# filters_V1_1.net
KiCad netlist of a schematic drawn in EAGLE
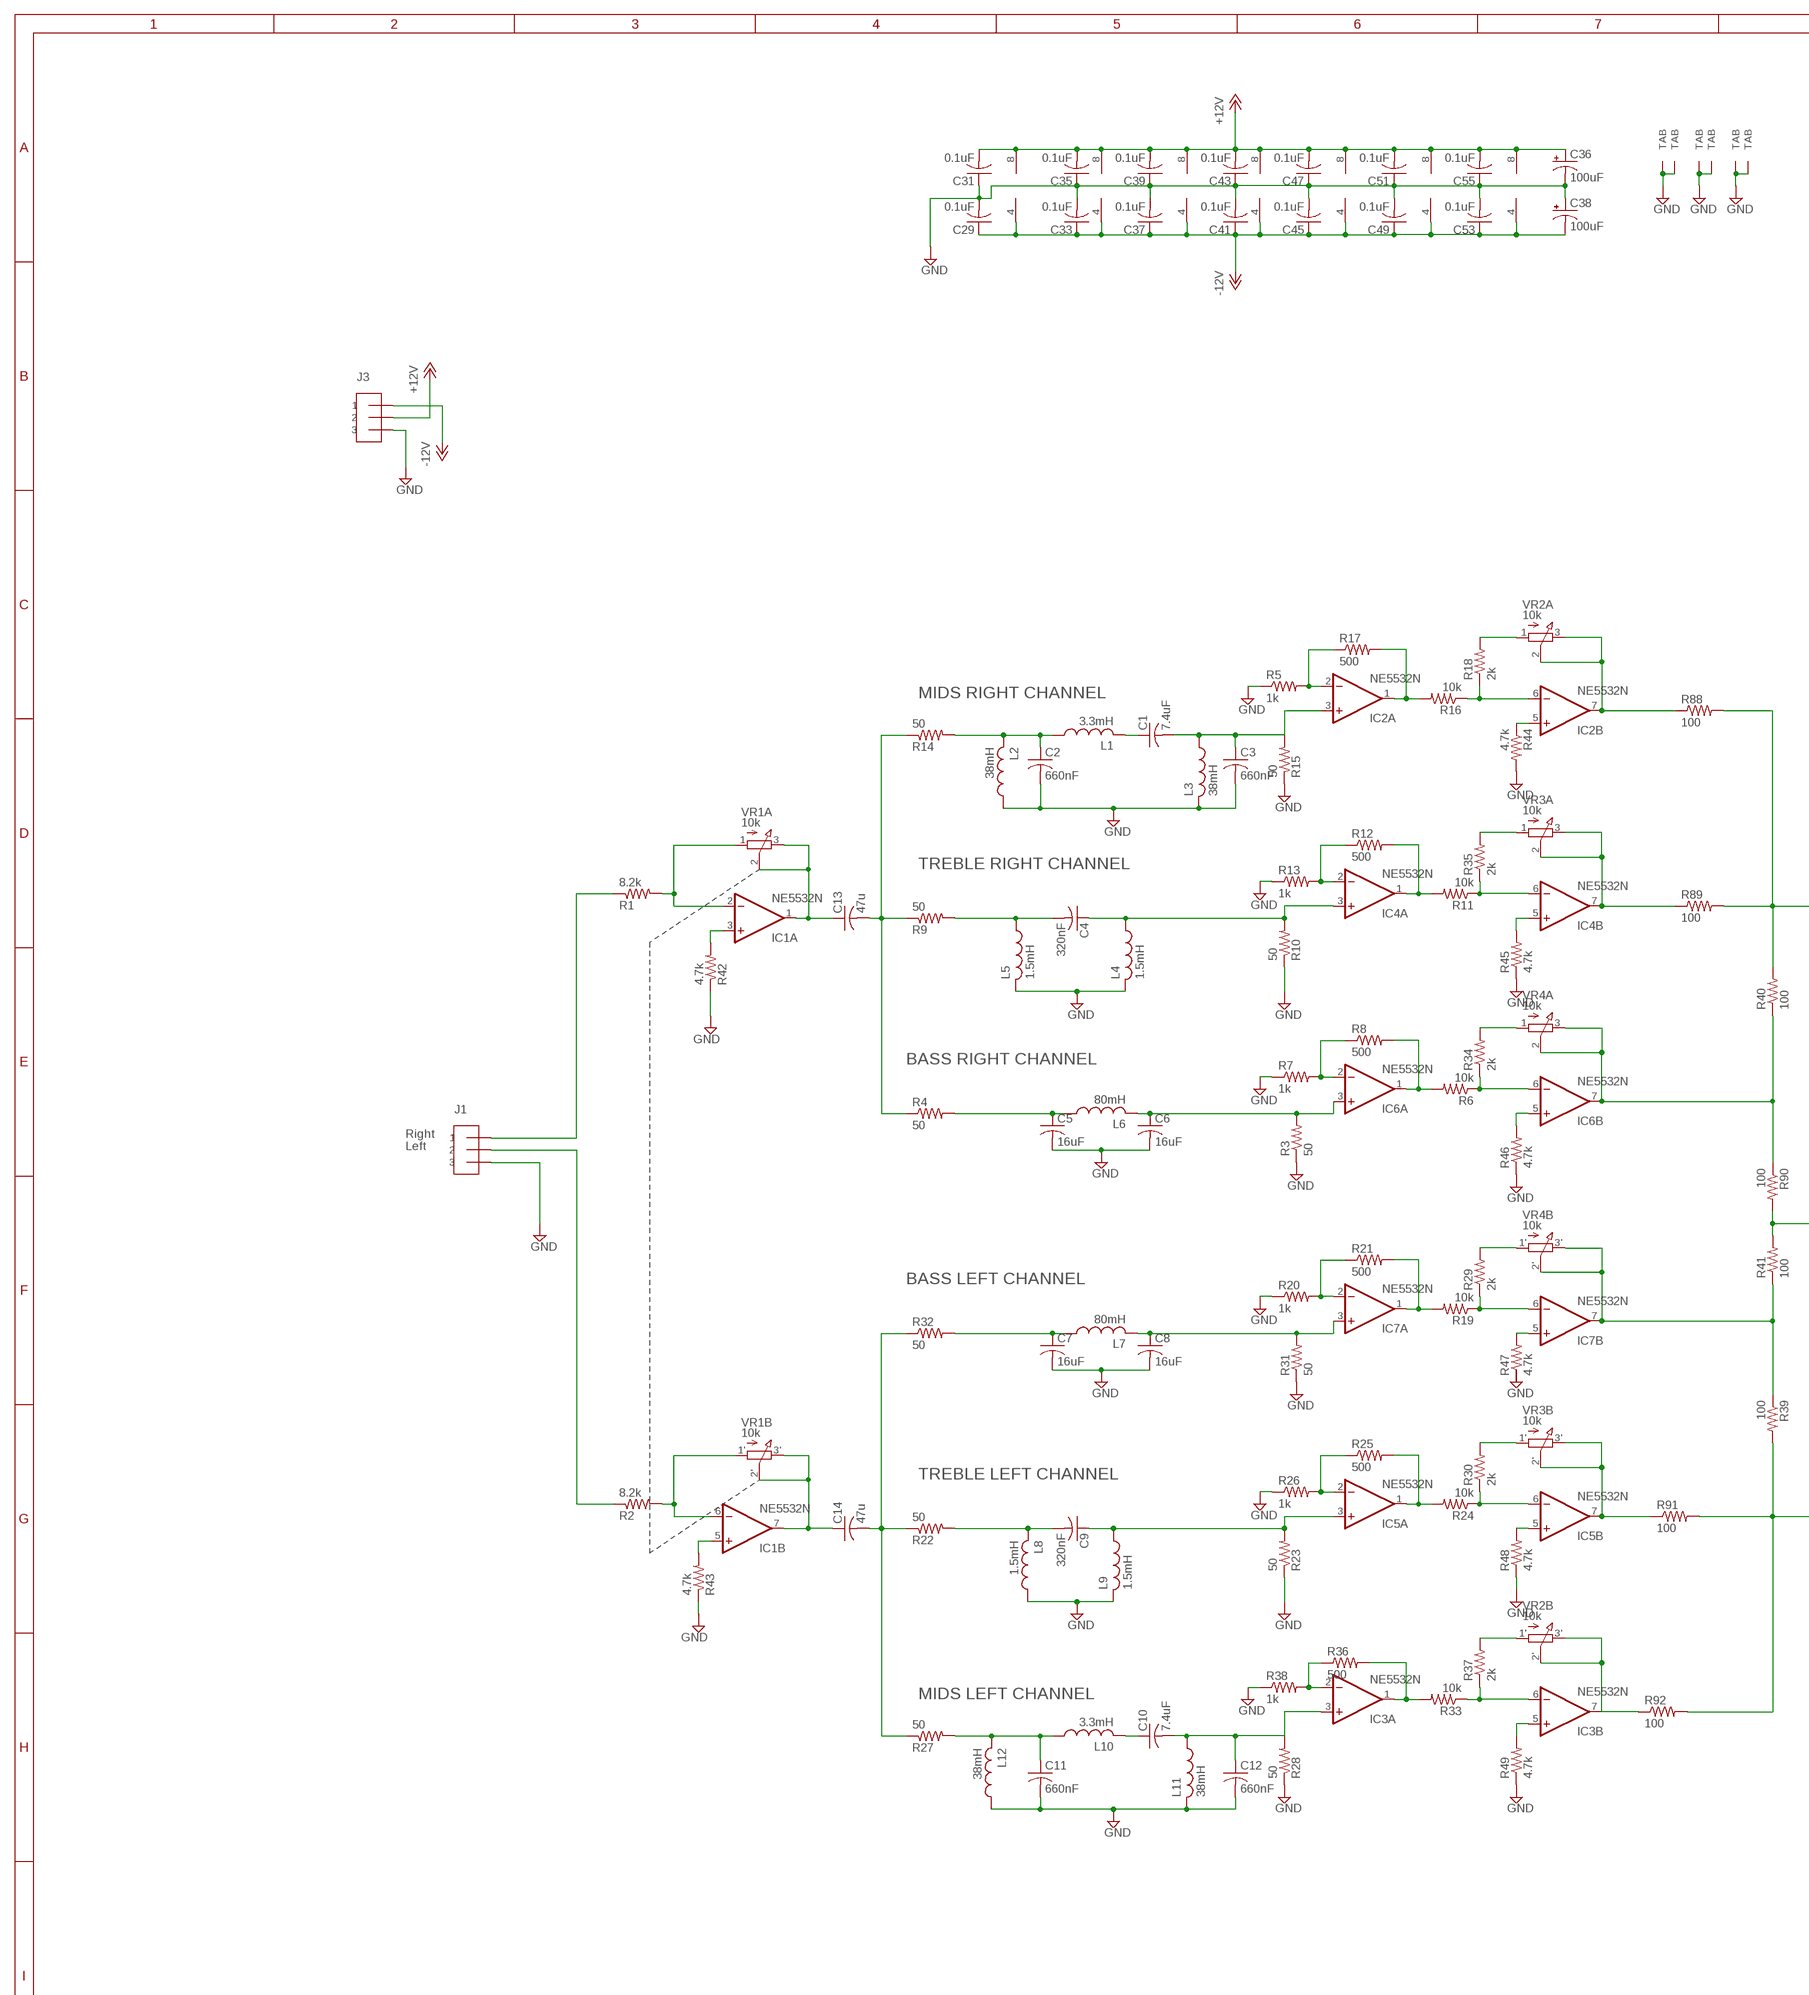
[diagram p0: schematic, sheet 1, part 1 of 2]
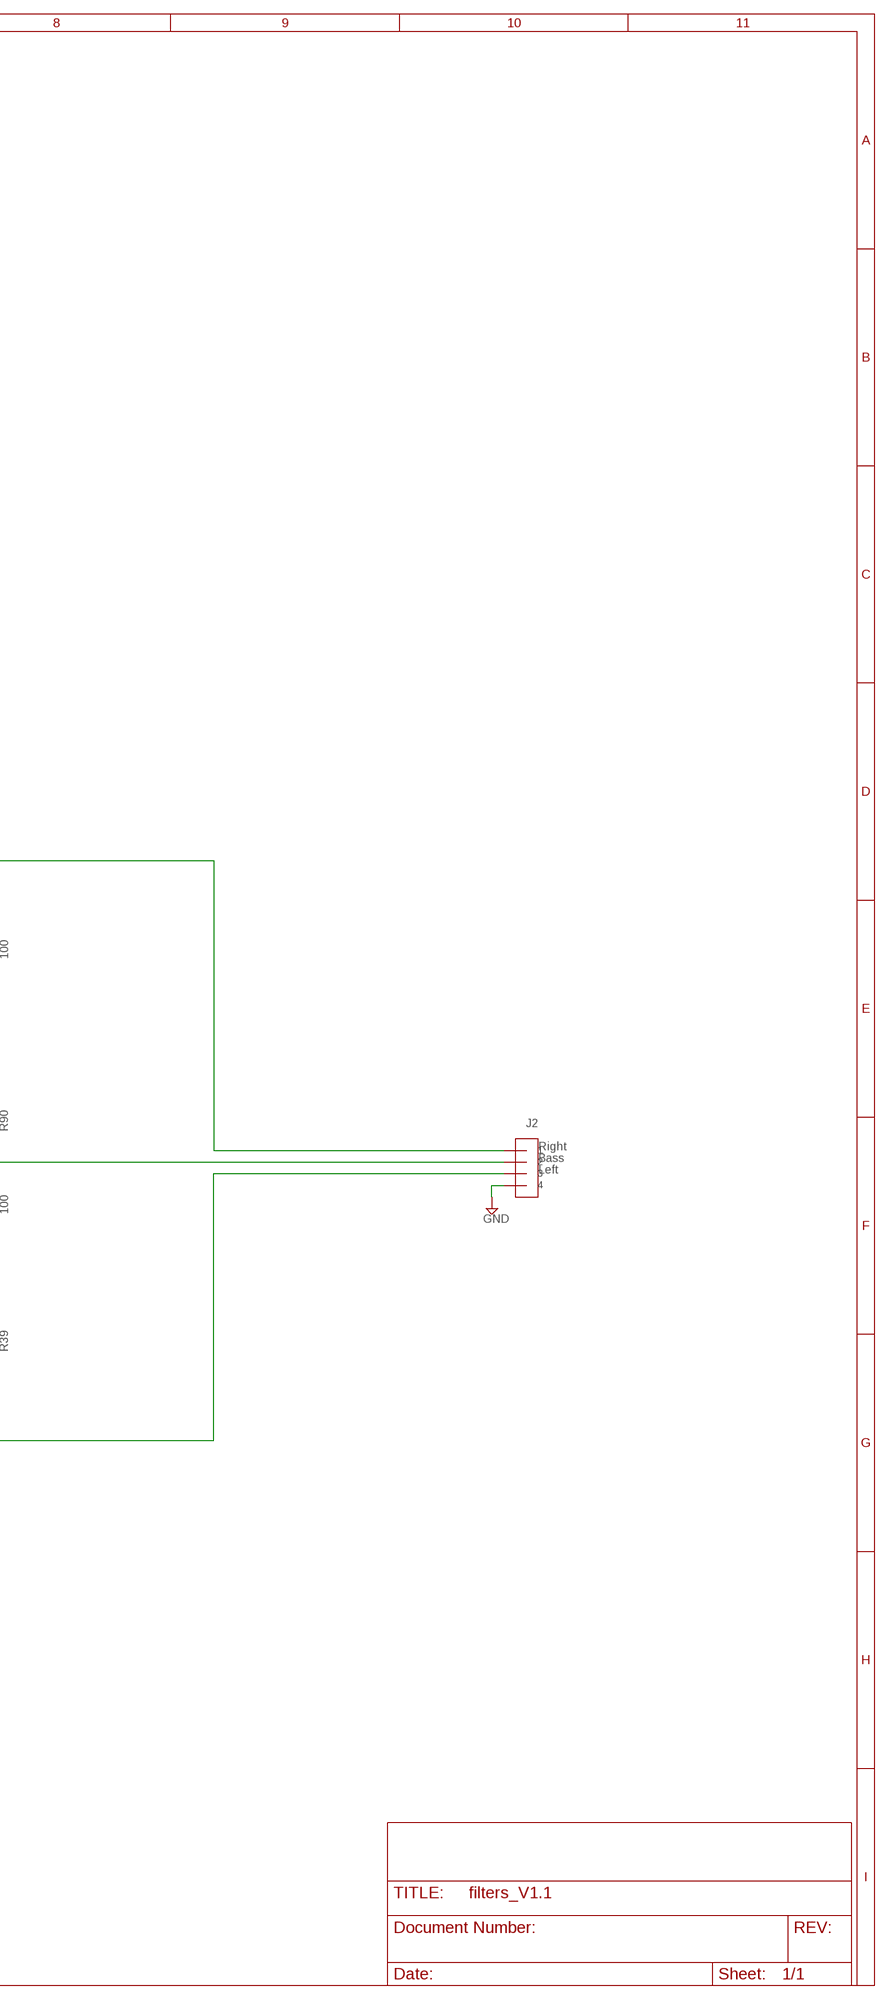
[diagram p1: schematic, sheet 1, part 2 of 2]

(export (version "E")
  (design (tool "Eeschema 10.0.6"))
  (components
    (comp (ref "C1")
      (value "7.4uF")
      (footprint "eagle-import:C050-024X044")
      (libsource (lib "eagle-import") (part "C-US050-024X044"))
    )
    (comp (ref "C2")
      (value "660nF")
      (footprint "eagle-import:C050-024X044")
      (libsource (lib "eagle-import") (part "C-US050-024X044"))
    )
    (comp (ref "C3")
      (value "660nF")
      (footprint "eagle-import:C050-024X044")
      (libsource (lib "eagle-import") (part "C-US050-024X044"))
    )
    (comp (ref "C4")
      (value "320nF")
      (footprint "eagle-import:C050-024X044")
      (libsource (lib "eagle-import") (part "C-US050-024X044"))
    )
    (comp (ref "C5")
      (value "16uF")
      (footprint "eagle-import:C050-024X044")
      (libsource (lib "eagle-import") (part "C-US050-024X044"))
    )
    (comp (ref "C6")
      (value "16uF")
      (footprint "eagle-import:C050-024X044")
      (libsource (lib "eagle-import") (part "C-US050-024X044"))
    )
    (comp (ref "C7")
      (value "16uF")
      (footprint "eagle-import:C050-024X044")
      (libsource (lib "eagle-import") (part "C-US050-024X044"))
    )
    (comp (ref "C8")
      (value "16uF")
      (footprint "eagle-import:C050-024X044")
      (libsource (lib "eagle-import") (part "C-US050-024X044"))
    )
    (comp (ref "C9")
      (value "320nF")
      (footprint "eagle-import:C050-024X044")
      (libsource (lib "eagle-import") (part "C-US050-024X044"))
    )
    (comp (ref "C10")
      (value "7.4uF")
      (footprint "eagle-import:C050-024X044")
      (libsource (lib "eagle-import") (part "C-US050-024X044"))
    )
    (comp (ref "C11")
      (value "660nF")
      (footprint "eagle-import:C050-024X044")
      (libsource (lib "eagle-import") (part "C-US050-024X044"))
    )
    (comp (ref "C12")
      (value "660nF")
      (footprint "eagle-import:C050-024X044")
      (libsource (lib "eagle-import") (part "C-US050-024X044"))
    )
    (comp (ref "C13")
      (value "47u")
      (footprint "eagle-import:C050-024X044")
      (libsource (lib "eagle-import") (part "C-US050-024X044"))
    )
    (comp (ref "C14")
      (value "47u")
      (footprint "eagle-import:C050-024X044")
      (libsource (lib "eagle-import") (part "C-US050-024X044"))
    )
    (comp (ref "C29")
      (value "0.1uF")
      (footprint "eagle-import:C050-024X044")
      (libsource (lib "eagle-import") (part "C-US050-024X044"))
    )
    (comp (ref "C31")
      (value "0.1uF")
      (footprint "eagle-import:C050-024X044")
      (libsource (lib "eagle-import") (part "C-US050-024X044"))
    )
    (comp (ref "C33")
      (value "0.1uF")
      (footprint "eagle-import:C050-024X044")
      (libsource (lib "eagle-import") (part "C-US050-024X044"))
    )
    (comp (ref "C35")
      (value "0.1uF")
      (footprint "eagle-import:C050-024X044")
      (libsource (lib "eagle-import") (part "C-US050-024X044"))
    )
    (comp (ref "C36")
      (value "100uF")
      (footprint "eagle-import:E2,5-6")
      (libsource (lib "eagle-import") (part "CPOL-USE2.5-6"))
    )
    (comp (ref "C37")
      (value "0.1uF")
      (footprint "eagle-import:C050-024X044")
      (libsource (lib "eagle-import") (part "C-US050-024X044"))
    )
    (comp (ref "C38")
      (value "100uF")
      (footprint "eagle-import:E2,5-6")
      (libsource (lib "eagle-import") (part "CPOL-USE2.5-6"))
    )
    (comp (ref "C39")
      (value "0.1uF")
      (footprint "eagle-import:C050-024X044")
      (libsource (lib "eagle-import") (part "C-US050-024X044"))
    )
    (comp (ref "C41")
      (value "0.1uF")
      (footprint "eagle-import:C050-024X044")
      (libsource (lib "eagle-import") (part "C-US050-024X044"))
    )
    (comp (ref "C43")
      (value "0.1uF")
      (footprint "eagle-import:C050-024X044")
      (libsource (lib "eagle-import") (part "C-US050-024X044"))
    )
    (comp (ref "C45")
      (value "0.1uF")
      (footprint "eagle-import:C050-024X044")
      (libsource (lib "eagle-import") (part "C-US050-024X044"))
    )
    (comp (ref "C47")
      (value "0.1uF")
      (footprint "eagle-import:C050-024X044")
      (libsource (lib "eagle-import") (part "C-US050-024X044"))
    )
    (comp (ref "C49")
      (value "0.1uF")
      (footprint "eagle-import:C050-024X044")
      (libsource (lib "eagle-import") (part "C-US050-024X044"))
    )
    (comp (ref "C51")
      (value "0.1uF")
      (footprint "eagle-import:C050-024X044")
      (libsource (lib "eagle-import") (part "C-US050-024X044"))
    )
    (comp (ref "C53")
      (value "0.1uF")
      (footprint "eagle-import:C050-024X044")
      (libsource (lib "eagle-import") (part "C-US050-024X044"))
    )
    (comp (ref "C55")
      (value "0.1uF")
      (footprint "eagle-import:C050-024X044")
      (libsource (lib "eagle-import") (part "C-US050-024X044"))
    )
    (comp (ref "IC1")
      (value "NE5532N")
      (footprint "eagle-import:DIL08")
      (libsource (lib "eagle-import") (part "NE5532N"))
    )
    (comp (ref "IC2")
      (value "NE5532N")
      (footprint "eagle-import:DIL08")
      (libsource (lib "eagle-import") (part "NE5532N"))
    )
    (comp (ref "IC3")
      (value "NE5532N")
      (footprint "eagle-import:DIL08")
      (libsource (lib "eagle-import") (part "NE5532N"))
    )
    (comp (ref "IC4")
      (value "NE5532N")
      (footprint "eagle-import:DIL08")
      (libsource (lib "eagle-import") (part "NE5532N"))
    )
    (comp (ref "IC5")
      (value "NE5532N")
      (footprint "eagle-import:DIL08")
      (libsource (lib "eagle-import") (part "NE5532N"))
    )
    (comp (ref "IC6")
      (value "NE5532N")
      (footprint "eagle-import:DIL08")
      (libsource (lib "eagle-import") (part "NE5532N"))
    )
    (comp (ref "IC7")
      (value "NE5532N")
      (footprint "eagle-import:DIL08")
      (libsource (lib "eagle-import") (part "NE5532N"))
    )
    (comp (ref "J1")
      (value "3_PIN_AMPCONN")
      (footprint "eagle-import:3_PIN_AMPCONN")
      (libsource (lib "eagle-import") (part "3_PIN_AMPCONN"))
    )
    (comp (ref "J2")
      (value "4_PIN_AMPCONN")
      (footprint "eagle-import:4_PIN_AMPCON")
      (libsource (lib "eagle-import") (part "4_PIN_AMPCONN"))
    )
    (comp (ref "J3")
      (value "3_PIN_AMPCONN")
      (footprint "eagle-import:3_PIN_AMPCONN")
      (libsource (lib "eagle-import") (part "3_PIN_AMPCONN"))
    )
    (comp (ref "L1")
      (value "3.3mH")
      (footprint "eagle-import:6000-XXXX-RC")
      (libsource (lib "eagle-import") (part "L-US6000-XXX-RC"))
    )
    (comp (ref "L2")
      (value "38mH")
      (footprint "eagle-import:6000-XXXX-RC")
      (libsource (lib "eagle-import") (part "L-US6000-XXX-RC"))
    )
    (comp (ref "L3")
      (value "38mH")
      (footprint "eagle-import:6000-XXXX-RC")
      (libsource (lib "eagle-import") (part "L-US6000-XXX-RC"))
    )
    (comp (ref "L4")
      (value "1.5mH")
      (footprint "eagle-import:6000-XXXX-RC")
      (libsource (lib "eagle-import") (part "L-US6000-XXX-RC"))
    )
    (comp (ref "L5")
      (value "1.5mH")
      (footprint "eagle-import:6000-XXXX-RC")
      (libsource (lib "eagle-import") (part "L-US6000-XXX-RC"))
    )
    (comp (ref "L6")
      (value "80mH")
      (footprint "eagle-import:6000-XXXX-RC")
      (libsource (lib "eagle-import") (part "L-US6000-XXX-RC"))
    )
    (comp (ref "L7")
      (value "80mH")
      (footprint "eagle-import:6000-XXXX-RC")
      (libsource (lib "eagle-import") (part "L-US6000-XXX-RC"))
    )
    (comp (ref "L8")
      (value "1.5mH")
      (footprint "eagle-import:6000-XXXX-RC")
      (libsource (lib "eagle-import") (part "L-US6000-XXX-RC"))
    )
    (comp (ref "L9")
      (value "1.5mH")
      (footprint "eagle-import:6000-XXXX-RC")
      (libsource (lib "eagle-import") (part "L-US6000-XXX-RC"))
    )
    (comp (ref "L10")
      (value "3.3mH")
      (footprint "eagle-import:6000-XXXX-RC")
      (libsource (lib "eagle-import") (part "L-US6000-XXX-RC"))
    )
    (comp (ref "L11")
      (value "38mH")
      (footprint "eagle-import:6000-XXXX-RC")
      (libsource (lib "eagle-import") (part "L-US6000-XXX-RC"))
    )
    (comp (ref "L12")
      (value "38mH")
      (footprint "eagle-import:6000-XXXX-RC")
      (libsource (lib "eagle-import") (part "L-US6000-XXX-RC"))
    )
    (comp (ref "R1")
      (value "8.2k")
      (footprint "eagle-import:0204V")
      (libsource (lib "eagle-import") (part "R-US_0204/2V"))
    )
    (comp (ref "R2")
      (value "8.2k")
      (footprint "eagle-import:0204V")
      (libsource (lib "eagle-import") (part "R-US_0204/2V"))
    )
    (comp (ref "R3")
      (value "50")
      (footprint "eagle-import:0204V")
      (libsource (lib "eagle-import") (part "R-US_0204/2V"))
    )
    (comp (ref "R4")
      (value "50")
      (footprint "eagle-import:0204V")
      (libsource (lib "eagle-import") (part "R-US_0204/2V"))
    )
    (comp (ref "R5")
      (value "1k")
      (footprint "eagle-import:0204V")
      (libsource (lib "eagle-import") (part "R-US_0204/2V"))
    )
    (comp (ref "R6")
      (value "10k")
      (footprint "eagle-import:0204V")
      (libsource (lib "eagle-import") (part "R-US_0204/2V"))
    )
    (comp (ref "R7")
      (value "1k")
      (footprint "eagle-import:0204V")
      (libsource (lib "eagle-import") (part "R-US_0204/2V"))
    )
    (comp (ref "R8")
      (value "500")
      (footprint "eagle-import:0204V")
      (libsource (lib "eagle-import") (part "R-US_0204/2V"))
    )
    (comp (ref "R9")
      (value "50")
      (footprint "eagle-import:0204V")
      (libsource (lib "eagle-import") (part "R-US_0204/2V"))
    )
    (comp (ref "R10")
      (value "50")
      (footprint "eagle-import:0204V")
      (libsource (lib "eagle-import") (part "R-US_0204/2V"))
    )
    (comp (ref "R11")
      (value "10k")
      (footprint "eagle-import:0204V")
      (libsource (lib "eagle-import") (part "R-US_0204/2V"))
    )
    (comp (ref "R12")
      (value "500")
      (footprint "eagle-import:0204V")
      (libsource (lib "eagle-import") (part "R-US_0204/2V"))
    )
    (comp (ref "R13")
      (value "1k")
      (footprint "eagle-import:0204V")
      (libsource (lib "eagle-import") (part "R-US_0204/2V"))
    )
    (comp (ref "R14")
      (value "50")
      (footprint "eagle-import:0204V")
      (libsource (lib "eagle-import") (part "R-US_0204/2V"))
    )
    (comp (ref "R15")
      (value "50")
      (footprint "eagle-import:0204V")
      (libsource (lib "eagle-import") (part "R-US_0204/2V"))
    )
    (comp (ref "R16")
      (value "10k")
      (footprint "eagle-import:0204V")
      (libsource (lib "eagle-import") (part "R-US_0204/2V"))
    )
    (comp (ref "R17")
      (value "500")
      (footprint "eagle-import:0204V")
      (libsource (lib "eagle-import") (part "R-US_0204/2V"))
    )
    (comp (ref "R18")
      (value "2k")
      (footprint "eagle-import:0204V")
      (libsource (lib "eagle-import") (part "R-US_0204/2V"))
    )
    (comp (ref "R19")
      (value "10k")
      (footprint "eagle-import:0204V")
      (libsource (lib "eagle-import") (part "R-US_0204/2V"))
    )
    (comp (ref "R20")
      (value "1k")
      (footprint "eagle-import:0204V")
      (libsource (lib "eagle-import") (part "R-US_0204/2V"))
    )
    (comp (ref "R21")
      (value "500")
      (footprint "eagle-import:0204V")
      (libsource (lib "eagle-import") (part "R-US_0204/2V"))
    )
    (comp (ref "R22")
      (value "50")
      (footprint "eagle-import:0204V")
      (libsource (lib "eagle-import") (part "R-US_0204/2V"))
    )
    (comp (ref "R23")
      (value "50")
      (footprint "eagle-import:0204V")
      (libsource (lib "eagle-import") (part "R-US_0204/2V"))
    )
    (comp (ref "R24")
      (value "10k")
      (footprint "eagle-import:0204V")
      (libsource (lib "eagle-import") (part "R-US_0204/2V"))
    )
    (comp (ref "R25")
      (value "500")
      (footprint "eagle-import:0204V")
      (libsource (lib "eagle-import") (part "R-US_0204/2V"))
    )
    (comp (ref "R26")
      (value "1k")
      (footprint "eagle-import:0204V")
      (libsource (lib "eagle-import") (part "R-US_0204/2V"))
    )
    (comp (ref "R27")
      (value "50")
      (footprint "eagle-import:0204V")
      (libsource (lib "eagle-import") (part "R-US_0204/2V"))
    )
    (comp (ref "R28")
      (value "50")
      (footprint "eagle-import:0204V")
      (libsource (lib "eagle-import") (part "R-US_0204/2V"))
    )
    (comp (ref "R29")
      (value "2k")
      (footprint "eagle-import:0204V")
      (libsource (lib "eagle-import") (part "R-US_0204/2V"))
    )
    (comp (ref "R30")
      (value "2k")
      (footprint "eagle-import:0204V")
      (libsource (lib "eagle-import") (part "R-US_0204/2V"))
    )
    (comp (ref "R31")
      (value "50")
      (footprint "eagle-import:0204V")
      (libsource (lib "eagle-import") (part "R-US_0204/2V"))
    )
    (comp (ref "R32")
      (value "50")
      (footprint "eagle-import:0204V")
      (libsource (lib "eagle-import") (part "R-US_0204/2V"))
    )
    (comp (ref "R33")
      (value "10k")
      (footprint "eagle-import:0204V")
      (libsource (lib "eagle-import") (part "R-US_0204/2V"))
    )
    (comp (ref "R34")
      (value "2k")
      (footprint "eagle-import:0204V")
      (libsource (lib "eagle-import") (part "R-US_0204/2V"))
    )
    (comp (ref "R35")
      (value "2k")
      (footprint "eagle-import:0204V")
      (libsource (lib "eagle-import") (part "R-US_0204/2V"))
    )
    (comp (ref "R36")
      (value "500")
      (footprint "eagle-import:0204V")
      (libsource (lib "eagle-import") (part "R-US_0204/2V"))
    )
    (comp (ref "R37")
      (value "2k")
      (footprint "eagle-import:0204V")
      (libsource (lib "eagle-import") (part "R-US_0204/2V"))
    )
    (comp (ref "R38")
      (value "1k")
      (footprint "eagle-import:0204V")
      (libsource (lib "eagle-import") (part "R-US_0204/2V"))
    )
    (comp (ref "R39")
      (value "100")
      (footprint "eagle-import:0204V")
      (libsource (lib "eagle-import") (part "R-US_0204/2V"))
    )
    (comp (ref "R40")
      (value "100")
      (footprint "eagle-import:0204V")
      (libsource (lib "eagle-import") (part "R-US_0204/2V"))
    )
    (comp (ref "R41")
      (value "100")
      (footprint "eagle-import:0204V")
      (libsource (lib "eagle-import") (part "R-US_0204/2V"))
    )
    (comp (ref "R42")
      (value "4.7k")
      (footprint "eagle-import:0204V")
      (libsource (lib "eagle-import") (part "R-US_0204/2V"))
    )
    (comp (ref "R43")
      (value "4.7k")
      (footprint "eagle-import:0204V")
      (libsource (lib "eagle-import") (part "R-US_0204/2V"))
    )
    (comp (ref "R44")
      (value "4.7k")
      (footprint "eagle-import:0204V")
      (libsource (lib "eagle-import") (part "R-US_0204/2V"))
    )
    (comp (ref "R45")
      (value "4.7k")
      (footprint "eagle-import:0204V")
      (libsource (lib "eagle-import") (part "R-US_0204/2V"))
    )
    (comp (ref "R46")
      (value "4.7k")
      (footprint "eagle-import:0204V")
      (libsource (lib "eagle-import") (part "R-US_0204/2V"))
    )
    (comp (ref "R47")
      (value "4.7k")
      (footprint "eagle-import:0204V")
      (libsource (lib "eagle-import") (part "R-US_0204/2V"))
    )
    (comp (ref "R48")
      (value "4.7k")
      (footprint "eagle-import:0204V")
      (libsource (lib "eagle-import") (part "R-US_0204/2V"))
    )
    (comp (ref "R49")
      (value "4.7k")
      (footprint "eagle-import:0204V")
      (libsource (lib "eagle-import") (part "R-US_0204/2V"))
    )
    (comp (ref "R88")
      (value "100")
      (footprint "eagle-import:0204V")
      (libsource (lib "eagle-import") (part "R-US_0204/2V"))
    )
    (comp (ref "R89")
      (value "100")
      (footprint "eagle-import:0204V")
      (libsource (lib "eagle-import") (part "R-US_0204/2V"))
    )
    (comp (ref "R90")
      (value "100")
      (footprint "eagle-import:0204V")
      (libsource (lib "eagle-import") (part "R-US_0204/2V"))
    )
    (comp (ref "R91")
      (value "100")
      (footprint "eagle-import:0204V")
      (libsource (lib "eagle-import") (part "R-US_0204/2V"))
    )
    (comp (ref "R92")
      (value "100")
      (footprint "eagle-import:0204V")
      (libsource (lib "eagle-import") (part "R-US_0204/2V"))
    )
    (comp (ref "VR1")
      (value "10k")
      (footprint "eagle-import:VOL_POT_2GANG")
      (libsource (lib "eagle-import") (part "VOL_POT_2GANG"))
    )
    (comp (ref "VR2")
      (value "10k")
      (footprint "eagle-import:TONE_POT_2GANG")
      (libsource (lib "eagle-import") (part "P140KV1-F25BR"))
    )
    (comp (ref "VR3")
      (value "10k")
      (footprint "eagle-import:TONE_POT_2GANG")
      (libsource (lib "eagle-import") (part "P140KV1-F25BR"))
    )
    (comp (ref "VR4")
      (value "10k")
      (footprint "eagle-import:TONE_POT_2GANG")
      (libsource (lib "eagle-import") (part "P140KV1-F25BR"))
    )
  )
  (nets
    (net (code "1") (name "+12V") (class "Default")
      (node (ref "C31") (pin "2") (pinfunction "2_2") (pintype "passive"))
      (node (ref "C35") (pin "2") (pinfunction "2_2") (pintype "passive"))
      (node (ref "C36") (pin "+") (pinfunction "+_+") (pintype "passive"))
      (node (ref "C39") (pin "2") (pinfunction "2_2") (pintype "passive"))
      (node (ref "C43") (pin "2") (pinfunction "2_2") (pintype "passive"))
      (node (ref "C47") (pin "2") (pinfunction "2_2") (pintype "passive"))
      (node (ref "C51") (pin "2") (pinfunction "2_2") (pintype "passive"))
      (node (ref "C55") (pin "2") (pinfunction "2_2") (pintype "passive"))
      (node (ref "IC1") (pin "8") (pinfunction "V+_8") (pintype "power_in"))
      (node (ref "IC2") (pin "8") (pinfunction "V+_8") (pintype "power_in"))
      (node (ref "IC3") (pin "8") (pinfunction "V+_8") (pintype "power_in"))
      (node (ref "IC4") (pin "8") (pinfunction "V+_8") (pintype "power_in"))
      (node (ref "IC5") (pin "8") (pinfunction "V+_8") (pintype "power_in"))
      (node (ref "IC6") (pin "8") (pinfunction "V+_8") (pintype "power_in"))
      (node (ref "IC7") (pin "8") (pinfunction "V+_8") (pintype "power_in"))
      (node (ref "J3") (pin "2") (pinfunction "2_2") (pintype "passive"))
    )
    (net (code "2") (name "-12V") (class "Default")
      (node (ref "C29") (pin "1") (pinfunction "1_1") (pintype "passive"))
      (node (ref "C33") (pin "1") (pinfunction "1_1") (pintype "passive"))
      (node (ref "C37") (pin "1") (pinfunction "1_1") (pintype "passive"))
      (node (ref "C38") (pin "-") (pinfunction "-_-") (pintype "passive"))
      (node (ref "C41") (pin "1") (pinfunction "1_1") (pintype "passive"))
      (node (ref "C45") (pin "1") (pinfunction "1_1") (pintype "passive"))
      (node (ref "C49") (pin "1") (pinfunction "1_1") (pintype "passive"))
      (node (ref "C53") (pin "1") (pinfunction "1_1") (pintype "passive"))
      (node (ref "IC1") (pin "4") (pinfunction "V-_4") (pintype "power_in"))
      (node (ref "IC2") (pin "4") (pinfunction "V-_4") (pintype "power_in"))
      (node (ref "IC3") (pin "4") (pinfunction "V-_4") (pintype "power_in"))
      (node (ref "IC4") (pin "4") (pinfunction "V-_4") (pintype "power_in"))
      (node (ref "IC5") (pin "4") (pinfunction "V-_4") (pintype "power_in"))
      (node (ref "IC6") (pin "4") (pinfunction "V-_4") (pintype "power_in"))
      (node (ref "IC7") (pin "4") (pinfunction "V-_4") (pintype "power_in"))
      (node (ref "J3") (pin "1") (pinfunction "1_1") (pintype "passive"))
    )
    (net (code "3") (name "GND") (class "Default")
      (node (ref "C11") (pin "2") (pinfunction "2_2") (pintype "passive"))
      (node (ref "C12") (pin "2") (pinfunction "2_2") (pintype "passive"))
      (node (ref "C2") (pin "2") (pinfunction "2_2") (pintype "passive"))
      (node (ref "C29") (pin "2") (pinfunction "2_2") (pintype "passive"))
      (node (ref "C3") (pin "2") (pinfunction "2_2") (pintype "passive"))
      (node (ref "C31") (pin "1") (pinfunction "1_1") (pintype "passive"))
      (node (ref "C33") (pin "2") (pinfunction "2_2") (pintype "passive"))
      (node (ref "C35") (pin "1") (pinfunction "1_1") (pintype "passive"))
      (node (ref "C36") (pin "-") (pinfunction "-_-") (pintype "passive"))
      (node (ref "C37") (pin "2") (pinfunction "2_2") (pintype "passive"))
      (node (ref "C38") (pin "+") (pinfunction "+_+") (pintype "passive"))
      (node (ref "C39") (pin "1") (pinfunction "1_1") (pintype "passive"))
      (node (ref "C41") (pin "2") (pinfunction "2_2") (pintype "passive"))
      (node (ref "C43") (pin "1") (pinfunction "1_1") (pintype "passive"))
      (node (ref "C45") (pin "2") (pinfunction "2_2") (pintype "passive"))
      (node (ref "C47") (pin "1") (pinfunction "1_1") (pintype "passive"))
      (node (ref "C49") (pin "2") (pinfunction "2_2") (pintype "passive"))
      (node (ref "C5") (pin "2") (pinfunction "2_2") (pintype "passive"))
      (node (ref "C51") (pin "1") (pinfunction "1_1") (pintype "passive"))
      (node (ref "C53") (pin "2") (pinfunction "2_2") (pintype "passive"))
      (node (ref "C55") (pin "1") (pinfunction "1_1") (pintype "passive"))
      (node (ref "C6") (pin "2") (pinfunction "2_2") (pintype "passive"))
      (node (ref "C7") (pin "2") (pinfunction "2_2") (pintype "passive"))
      (node (ref "C8") (pin "2") (pinfunction "2_2") (pintype "passive"))
      (node (ref "J1") (pin "3") (pinfunction "3_3") (pintype "passive"))
      (node (ref "J2") (pin "4") (pinfunction "4_4") (pintype "passive"))
      (node (ref "J3") (pin "3") (pinfunction "3_3") (pintype "passive"))
      (node (ref "L11") (pin "2") (pinfunction "2_2") (pintype "passive"))
      (node (ref "L12") (pin "1") (pinfunction "1_1") (pintype "passive"))
      (node (ref "L2") (pin "1") (pinfunction "1_1") (pintype "passive"))
      (node (ref "L3") (pin "2") (pinfunction "2_2") (pintype "passive"))
      (node (ref "L4") (pin "2") (pinfunction "2_2") (pintype "passive"))
      (node (ref "L5") (pin "2") (pinfunction "2_2") (pintype "passive"))
      (node (ref "L8") (pin "1") (pinfunction "1_1") (pintype "passive"))
      (node (ref "L9") (pin "2") (pinfunction "2_2") (pintype "passive"))
      (node (ref "R10") (pin "1") (pinfunction "1_1") (pintype "passive"))
      (node (ref "R13") (pin "1") (pinfunction "1_1") (pintype "passive"))
      (node (ref "R15") (pin "1") (pinfunction "1_1") (pintype "passive"))
      (node (ref "R20") (pin "1") (pinfunction "1_1") (pintype "passive"))
      (node (ref "R23") (pin "1") (pinfunction "1_1") (pintype "passive"))
      (node (ref "R26") (pin "1") (pinfunction "1_1") (pintype "passive"))
      (node (ref "R28") (pin "1") (pinfunction "1_1") (pintype "passive"))
      (node (ref "R3") (pin "1") (pinfunction "1_1") (pintype "passive"))
      (node (ref "R31") (pin "1") (pinfunction "1_1") (pintype "passive"))
      (node (ref "R38") (pin "1") (pinfunction "1_1") (pintype "passive"))
      (node (ref "R42") (pin "1") (pinfunction "1_1") (pintype "passive"))
      (node (ref "R43") (pin "1") (pinfunction "1_1") (pintype "passive"))
      (node (ref "R44") (pin "2") (pinfunction "2_2") (pintype "passive"))
      (node (ref "R45") (pin "1") (pinfunction "1_1") (pintype "passive"))
      (node (ref "R46") (pin "1") (pinfunction "1_1") (pintype "passive"))
      (node (ref "R48") (pin "1") (pinfunction "1_1") (pintype "passive"))
      (node (ref "R49") (pin "1") (pinfunction "1_1") (pintype "passive"))
      (node (ref "R5") (pin "1") (pinfunction "1_1") (pintype "passive"))
      (node (ref "R7") (pin "1") (pinfunction "1_1") (pintype "passive"))
      (node (ref "VR2") (pin "P$3") (pinfunction "TAB_P$3") (pintype "passive"))
      (node (ref "VR2") (pin "P$4") (pinfunction "TAB_P$4") (pintype "passive"))
      (node (ref "VR3") (pin "P$3") (pinfunction "TAB_P$3") (pintype "passive"))
      (node (ref "VR3") (pin "P$4") (pinfunction "TAB_P$4") (pintype "passive"))
      (node (ref "VR4") (pin "P$3") (pinfunction "TAB_P$3") (pintype "passive"))
      (node (ref "VR4") (pin "P$4") (pinfunction "TAB_P$4") (pintype "passive"))
    )
    (net (code "4") (name "Net-(C1-Pad1)") (class "Default")
      (node (ref "C1") (pin "1") (pinfunction "1_1") (pintype "passive"))
      (node (ref "L1") (pin "2") (pinfunction "2_2") (pintype "passive"))
    )
    (net (code "5") (name "Net-(C2-Pad1)") (class "Default")
      (node (ref "C2") (pin "1") (pinfunction "1_1") (pintype "passive"))
      (node (ref "L1") (pin "1") (pinfunction "1_1") (pintype "passive"))
      (node (ref "L2") (pin "2") (pinfunction "2_2") (pintype "passive"))
      (node (ref "R14") (pin "2") (pinfunction "2_2") (pintype "passive"))
    )
    (net (code "6") (name "Net-(C4-Pad2)") (class "Default")
      (node (ref "C4") (pin "2") (pinfunction "2_2") (pintype "passive"))
      (node (ref "L5") (pin "1") (pinfunction "1_1") (pintype "passive"))
      (node (ref "R9") (pin "2") (pinfunction "2_2") (pintype "passive"))
    )
    (net (code "7") (name "Net-(C5-Pad1)") (class "Default")
      (node (ref "C5") (pin "1") (pinfunction "1_1") (pintype "passive"))
      (node (ref "L6") (pin "1") (pinfunction "1_1") (pintype "passive"))
      (node (ref "R4") (pin "2") (pinfunction "2_2") (pintype "passive"))
    )
    (net (code "8") (name "Net-(C7-Pad1)") (class "Default")
      (node (ref "C7") (pin "1") (pinfunction "1_1") (pintype "passive"))
      (node (ref "L7") (pin "1") (pinfunction "1_1") (pintype "passive"))
      (node (ref "R32") (pin "2") (pinfunction "2_2") (pintype "passive"))
    )
    (net (code "9") (name "Net-(C9-Pad2)") (class "Default")
      (node (ref "C9") (pin "2") (pinfunction "2_2") (pintype "passive"))
      (node (ref "L8") (pin "2") (pinfunction "2_2") (pintype "passive"))
      (node (ref "R22") (pin "2") (pinfunction "2_2") (pintype "passive"))
    )
    (net (code "10") (name "Net-(C10-Pad1)") (class "Default")
      (node (ref "C10") (pin "1") (pinfunction "1_1") (pintype "passive"))
      (node (ref "L10") (pin "2") (pinfunction "2_2") (pintype "passive"))
    )
    (net (code "11") (name "Net-(C11-Pad1)") (class "Default")
      (node (ref "C11") (pin "1") (pinfunction "1_1") (pintype "passive"))
      (node (ref "L10") (pin "1") (pinfunction "1_1") (pintype "passive"))
      (node (ref "L12") (pin "2") (pinfunction "2_2") (pintype "passive"))
      (node (ref "R27") (pin "2") (pinfunction "2_2") (pintype "passive"))
    )
    (net (code "12") (name "Net-(C13-Pad2)") (class "Default")
      (node (ref "C13") (pin "2") (pinfunction "2_2") (pintype "passive"))
      (node (ref "R14") (pin "1") (pinfunction "1_1") (pintype "passive"))
      (node (ref "R4") (pin "1") (pinfunction "1_1") (pintype "passive"))
      (node (ref "R9") (pin "1") (pinfunction "1_1") (pintype "passive"))
    )
    (net (code "13") (name "Net-(C14-Pad2)") (class "Default")
      (node (ref "C14") (pin "2") (pinfunction "2_2") (pintype "passive"))
      (node (ref "R22") (pin "1") (pinfunction "1_1") (pintype "passive"))
      (node (ref "R27") (pin "1") (pinfunction "1_1") (pintype "passive"))
      (node (ref "R32") (pin "1") (pinfunction "1_1") (pintype "passive"))
    )
    (net (code "14") (name "Net-(IC1A-+IN)") (class "Default")
      (node (ref "IC1") (pin "3") (pinfunction "+IN_3") (pintype "input"))
      (node (ref "R42") (pin "2") (pinfunction "2_2") (pintype "passive"))
    )
    (net (code "15") (name "Net-(IC1A--IN)") (class "Default")
      (node (ref "IC1") (pin "2") (pinfunction "-IN_2") (pintype "input"))
      (node (ref "R1") (pin "2") (pinfunction "2_2") (pintype "passive"))
      (node (ref "VR1") (pin "1") (pinfunction "1_1") (pintype "passive"))
    )
    (net (code "16") (name "Net-(IC1A-OUT)") (class "Default")
      (node (ref "C13") (pin "1") (pinfunction "1_1") (pintype "passive"))
      (node (ref "IC1") (pin "1") (pinfunction "OUT_1") (pintype "output"))
      (node (ref "VR1") (pin "2") (pinfunction "2_2") (pintype "passive"))
      (node (ref "VR1") (pin "3") (pinfunction "3_3") (pintype "passive"))
    )
    (net (code "17") (name "Net-(IC1B-+IN)") (class "Default")
      (node (ref "IC1") (pin "5") (pinfunction "+IN_5") (pintype "input"))
      (node (ref "R43") (pin "2") (pinfunction "2_2") (pintype "passive"))
    )
    (net (code "18") (name "Net-(IC1B--IN)") (class "Default")
      (node (ref "IC1") (pin "6") (pinfunction "-IN_6") (pintype "input"))
      (node (ref "R2") (pin "2") (pinfunction "2_2") (pintype "passive"))
      (node (ref "VR1") (pin "1'") (pinfunction "1_1'") (pintype "passive"))
    )
    (net (code "19") (name "Net-(IC1B-OUT)") (class "Default")
      (node (ref "C14") (pin "1") (pinfunction "1_1") (pintype "passive"))
      (node (ref "IC1") (pin "7") (pinfunction "OUT_7") (pintype "output"))
      (node (ref "VR1") (pin "2'") (pinfunction "2_2'") (pintype "passive"))
      (node (ref "VR1") (pin "3'") (pinfunction "3_3'") (pintype "passive"))
    )
    (net (code "20") (name "Net-(IC2A-+IN)") (class "Default")
      (node (ref "C1") (pin "2") (pinfunction "2_2") (pintype "passive"))
      (node (ref "C3") (pin "1") (pinfunction "1_1") (pintype "passive"))
      (node (ref "IC2") (pin "3") (pinfunction "+IN_3") (pintype "input"))
      (node (ref "L3") (pin "1") (pinfunction "1_1") (pintype "passive"))
      (node (ref "R15") (pin "2") (pinfunction "2_2") (pintype "passive"))
    )
    (net (code "21") (name "Net-(IC2A--IN)") (class "Default")
      (node (ref "IC2") (pin "2") (pinfunction "-IN_2") (pintype "input"))
      (node (ref "R17") (pin "1") (pinfunction "1_1") (pintype "passive"))
      (node (ref "R5") (pin "2") (pinfunction "2_2") (pintype "passive"))
    )
    (net (code "22") (name "Net-(IC2A-OUT)") (class "Default")
      (node (ref "IC2") (pin "1") (pinfunction "OUT_1") (pintype "output"))
      (node (ref "R16") (pin "2") (pinfunction "2_2") (pintype "passive"))
      (node (ref "R17") (pin "2") (pinfunction "2_2") (pintype "passive"))
    )
    (net (code "23") (name "Net-(IC2B-+IN)") (class "Default")
      (node (ref "IC2") (pin "5") (pinfunction "+IN_5") (pintype "input"))
      (node (ref "R44") (pin "1") (pinfunction "1_1") (pintype "passive"))
    )
    (net (code "24") (name "Net-(IC2B--IN)") (class "Default")
      (node (ref "IC2") (pin "6") (pinfunction "-IN_6") (pintype "input"))
      (node (ref "R16") (pin "1") (pinfunction "1_1") (pintype "passive"))
      (node (ref "R18") (pin "1") (pinfunction "1_1") (pintype "passive"))
    )
    (net (code "25") (name "Net-(IC2B-OUT)") (class "Default")
      (node (ref "IC2") (pin "7") (pinfunction "OUT_7") (pintype "output"))
      (node (ref "R88") (pin "1") (pinfunction "1_1") (pintype "passive"))
      (node (ref "VR2") (pin "2") (pinfunction "1_2_2") (pintype "passive"))
      (node (ref "VR2") (pin "3") (pinfunction "1_3_3") (pintype "passive"))
    )
    (net (code "26") (name "Net-(IC3A-+IN)") (class "Default")
      (node (ref "C10") (pin "2") (pinfunction "2_2") (pintype "passive"))
      (node (ref "C12") (pin "1") (pinfunction "1_1") (pintype "passive"))
      (node (ref "IC3") (pin "3") (pinfunction "+IN_3") (pintype "input"))
      (node (ref "L11") (pin "1") (pinfunction "1_1") (pintype "passive"))
      (node (ref "R28") (pin "2") (pinfunction "2_2") (pintype "passive"))
    )
    (net (code "27") (name "Net-(IC3A--IN)") (class "Default")
      (node (ref "IC3") (pin "2") (pinfunction "-IN_2") (pintype "input"))
      (node (ref "R36") (pin "1") (pinfunction "1_1") (pintype "passive"))
      (node (ref "R38") (pin "2") (pinfunction "2_2") (pintype "passive"))
    )
    (net (code "28") (name "Net-(IC3A-OUT)") (class "Default")
      (node (ref "IC3") (pin "1") (pinfunction "OUT_1") (pintype "output"))
      (node (ref "R33") (pin "2") (pinfunction "2_2") (pintype "passive"))
      (node (ref "R36") (pin "2") (pinfunction "2_2") (pintype "passive"))
    )
    (net (code "29") (name "Net-(IC3B-+IN)") (class "Default")
      (node (ref "IC3") (pin "5") (pinfunction "+IN_5") (pintype "input"))
      (node (ref "R49") (pin "2") (pinfunction "2_2") (pintype "passive"))
    )
    (net (code "30") (name "Net-(IC3B--IN)") (class "Default")
      (node (ref "IC3") (pin "6") (pinfunction "-IN_6") (pintype "input"))
      (node (ref "R33") (pin "1") (pinfunction "1_1") (pintype "passive"))
      (node (ref "R37") (pin "1") (pinfunction "1_1") (pintype "passive"))
    )
    (net (code "31") (name "Net-(IC3B-OUT)") (class "Default")
      (node (ref "IC3") (pin "7") (pinfunction "OUT_7") (pintype "output"))
      (node (ref "R92") (pin "1") (pinfunction "1_1") (pintype "passive"))
      (node (ref "VR2") (pin "2'") (pinfunction "1_2_2'") (pintype "passive"))
      (node (ref "VR2") (pin "3'") (pinfunction "1_3_3'") (pintype "passive"))
    )
    (net (code "32") (name "Net-(IC4A-+IN)") (class "Default")
      (node (ref "C4") (pin "1") (pinfunction "1_1") (pintype "passive"))
      (node (ref "IC4") (pin "3") (pinfunction "+IN_3") (pintype "input"))
      (node (ref "L4") (pin "1") (pinfunction "1_1") (pintype "passive"))
      (node (ref "R10") (pin "2") (pinfunction "2_2") (pintype "passive"))
    )
    (net (code "33") (name "Net-(IC4A--IN)") (class "Default")
      (node (ref "IC4") (pin "2") (pinfunction "-IN_2") (pintype "input"))
      (node (ref "R12") (pin "1") (pinfunction "1_1") (pintype "passive"))
      (node (ref "R13") (pin "2") (pinfunction "2_2") (pintype "passive"))
    )
    (net (code "34") (name "Net-(IC4A-OUT)") (class "Default")
      (node (ref "IC4") (pin "1") (pinfunction "OUT_1") (pintype "output"))
      (node (ref "R11") (pin "2") (pinfunction "2_2") (pintype "passive"))
      (node (ref "R12") (pin "2") (pinfunction "2_2") (pintype "passive"))
    )
    (net (code "35") (name "Net-(IC4B-+IN)") (class "Default")
      (node (ref "IC4") (pin "5") (pinfunction "+IN_5") (pintype "input"))
      (node (ref "R45") (pin "2") (pinfunction "2_2") (pintype "passive"))
    )
    (net (code "36") (name "Net-(IC4B--IN)") (class "Default")
      (node (ref "IC4") (pin "6") (pinfunction "-IN_6") (pintype "input"))
      (node (ref "R11") (pin "1") (pinfunction "1_1") (pintype "passive"))
      (node (ref "R35") (pin "1") (pinfunction "1_1") (pintype "passive"))
    )
    (net (code "37") (name "Net-(IC4B-OUT)") (class "Default")
      (node (ref "IC4") (pin "7") (pinfunction "OUT_7") (pintype "output"))
      (node (ref "R89") (pin "1") (pinfunction "1_1") (pintype "passive"))
      (node (ref "VR3") (pin "2") (pinfunction "1_2_2") (pintype "passive"))
      (node (ref "VR3") (pin "3") (pinfunction "1_3_3") (pintype "passive"))
    )
    (net (code "38") (name "Net-(IC5A-+IN)") (class "Default")
      (node (ref "C9") (pin "1") (pinfunction "1_1") (pintype "passive"))
      (node (ref "IC5") (pin "3") (pinfunction "+IN_3") (pintype "input"))
      (node (ref "L9") (pin "1") (pinfunction "1_1") (pintype "passive"))
      (node (ref "R23") (pin "2") (pinfunction "2_2") (pintype "passive"))
    )
    (net (code "39") (name "Net-(IC5A--IN)") (class "Default")
      (node (ref "IC5") (pin "2") (pinfunction "-IN_2") (pintype "input"))
      (node (ref "R25") (pin "1") (pinfunction "1_1") (pintype "passive"))
      (node (ref "R26") (pin "2") (pinfunction "2_2") (pintype "passive"))
    )
    (net (code "40") (name "Net-(IC5A-OUT)") (class "Default")
      (node (ref "IC5") (pin "1") (pinfunction "OUT_1") (pintype "output"))
      (node (ref "R24") (pin "2") (pinfunction "2_2") (pintype "passive"))
      (node (ref "R25") (pin "2") (pinfunction "2_2") (pintype "passive"))
    )
    (net (code "41") (name "Net-(IC5B-+IN)") (class "Default")
      (node (ref "IC5") (pin "5") (pinfunction "+IN_5") (pintype "input"))
      (node (ref "R48") (pin "2") (pinfunction "2_2") (pintype "passive"))
    )
    (net (code "42") (name "Net-(IC5B--IN)") (class "Default")
      (node (ref "IC5") (pin "6") (pinfunction "-IN_6") (pintype "input"))
      (node (ref "R24") (pin "1") (pinfunction "1_1") (pintype "passive"))
      (node (ref "R30") (pin "1") (pinfunction "1_1") (pintype "passive"))
    )
    (net (code "43") (name "Net-(IC5B-OUT)") (class "Default")
      (node (ref "IC5") (pin "7") (pinfunction "OUT_7") (pintype "output"))
      (node (ref "R91") (pin "1") (pinfunction "1_1") (pintype "passive"))
      (node (ref "VR3") (pin "2'") (pinfunction "1_2_2'") (pintype "passive"))
      (node (ref "VR3") (pin "3'") (pinfunction "1_3_3'") (pintype "passive"))
    )
    (net (code "44") (name "Net-(IC6A-+IN)") (class "Default")
      (node (ref "C6") (pin "1") (pinfunction "1_1") (pintype "passive"))
      (node (ref "IC6") (pin "3") (pinfunction "+IN_3") (pintype "input"))
      (node (ref "L6") (pin "2") (pinfunction "2_2") (pintype "passive"))
      (node (ref "R3") (pin "2") (pinfunction "2_2") (pintype "passive"))
    )
    (net (code "45") (name "Net-(IC6A--IN)") (class "Default")
      (node (ref "IC6") (pin "2") (pinfunction "-IN_2") (pintype "input"))
      (node (ref "R7") (pin "2") (pinfunction "2_2") (pintype "passive"))
      (node (ref "R8") (pin "1") (pinfunction "1_1") (pintype "passive"))
    )
    (net (code "46") (name "Net-(IC6A-OUT)") (class "Default")
      (node (ref "IC6") (pin "1") (pinfunction "OUT_1") (pintype "output"))
      (node (ref "R6") (pin "2") (pinfunction "2_2") (pintype "passive"))
      (node (ref "R8") (pin "2") (pinfunction "2_2") (pintype "passive"))
    )
    (net (code "47") (name "Net-(IC6B-+IN)") (class "Default")
      (node (ref "IC6") (pin "5") (pinfunction "+IN_5") (pintype "input"))
      (node (ref "R46") (pin "2") (pinfunction "2_2") (pintype "passive"))
    )
    (net (code "48") (name "Net-(IC6B--IN)") (class "Default")
      (node (ref "IC6") (pin "6") (pinfunction "-IN_6") (pintype "input"))
      (node (ref "R34") (pin "1") (pinfunction "1_1") (pintype "passive"))
      (node (ref "R6") (pin "1") (pinfunction "1_1") (pintype "passive"))
    )
    (net (code "49") (name "Net-(IC6B-OUT)") (class "Default")
      (node (ref "IC6") (pin "7") (pinfunction "OUT_7") (pintype "output"))
      (node (ref "R40") (pin "1") (pinfunction "1_1") (pintype "passive"))
      (node (ref "R90") (pin "1") (pinfunction "1_1") (pintype "passive"))
      (node (ref "VR4") (pin "2") (pinfunction "1_2_2") (pintype "passive"))
      (node (ref "VR4") (pin "3") (pinfunction "1_3_3") (pintype "passive"))
    )
    (net (code "50") (name "Net-(IC7A-+IN)") (class "Default")
      (node (ref "C8") (pin "1") (pinfunction "1_1") (pintype "passive"))
      (node (ref "IC7") (pin "3") (pinfunction "+IN_3") (pintype "input"))
      (node (ref "L7") (pin "2") (pinfunction "2_2") (pintype "passive"))
      (node (ref "R31") (pin "2") (pinfunction "2_2") (pintype "passive"))
    )
    (net (code "51") (name "Net-(IC7A--IN)") (class "Default")
      (node (ref "IC7") (pin "2") (pinfunction "-IN_2") (pintype "input"))
      (node (ref "R20") (pin "2") (pinfunction "2_2") (pintype "passive"))
      (node (ref "R21") (pin "1") (pinfunction "1_1") (pintype "passive"))
    )
    (net (code "52") (name "Net-(IC7A-OUT)") (class "Default")
      (node (ref "IC7") (pin "1") (pinfunction "OUT_1") (pintype "output"))
      (node (ref "R19") (pin "2") (pinfunction "2_2") (pintype "passive"))
      (node (ref "R21") (pin "2") (pinfunction "2_2") (pintype "passive"))
    )
    (net (code "53") (name "Net-(IC7B-+IN)") (class "Default")
      (node (ref "IC7") (pin "5") (pinfunction "+IN_5") (pintype "input"))
      (node (ref "R47") (pin "2") (pinfunction "2_2") (pintype "passive"))
    )
    (net (code "54") (name "Net-(IC7B--IN)") (class "Default")
      (node (ref "IC7") (pin "6") (pinfunction "-IN_6") (pintype "input"))
      (node (ref "R19") (pin "1") (pinfunction "1_1") (pintype "passive"))
      (node (ref "R29") (pin "1") (pinfunction "1_1") (pintype "passive"))
    )
    (net (code "55") (name "Net-(IC7B-OUT)") (class "Default")
      (node (ref "IC7") (pin "7") (pinfunction "OUT_7") (pintype "output"))
      (node (ref "R39") (pin "1") (pinfunction "1_1") (pintype "passive"))
      (node (ref "R41") (pin "1") (pinfunction "1_1") (pintype "passive"))
      (node (ref "VR4") (pin "2'") (pinfunction "1_2_2'") (pintype "passive"))
      (node (ref "VR4") (pin "3'") (pinfunction "1_3_3'") (pintype "passive"))
    )
    (net (code "56") (name "Net-(J1-Pad1)") (class "Default")
      (node (ref "J1") (pin "1") (pinfunction "1_1") (pintype "passive"))
      (node (ref "R1") (pin "1") (pinfunction "1_1") (pintype "passive"))
    )
    (net (code "57") (name "Net-(J1-Pad2)") (class "Default")
      (node (ref "J1") (pin "2") (pinfunction "2_2") (pintype "passive"))
      (node (ref "R2") (pin "1") (pinfunction "1_1") (pintype "passive"))
    )
    (net (code "58") (name "Net-(J2-Pad1)") (class "Default")
      (node (ref "J2") (pin "1") (pinfunction "1_1") (pintype "passive"))
      (node (ref "R40") (pin "2") (pinfunction "2_2") (pintype "passive"))
      (node (ref "R88") (pin "2") (pinfunction "2_2") (pintype "passive"))
      (node (ref "R89") (pin "2") (pinfunction "2_2") (pintype "passive"))
    )
    (net (code "59") (name "Net-(J2-Pad2)") (class "Default")
      (node (ref "J2") (pin "2") (pinfunction "2_2") (pintype "passive"))
      (node (ref "R41") (pin "2") (pinfunction "2_2") (pintype "passive"))
      (node (ref "R90") (pin "2") (pinfunction "2_2") (pintype "passive"))
    )
    (net (code "60") (name "Net-(J2-Pad3)") (class "Default")
      (node (ref "J2") (pin "3") (pinfunction "3_3") (pintype "passive"))
      (node (ref "R39") (pin "2") (pinfunction "2_2") (pintype "passive"))
      (node (ref "R91") (pin "2") (pinfunction "2_2") (pintype "passive"))
      (node (ref "R92") (pin "2") (pinfunction "2_2") (pintype "passive"))
    )
    (net (code "61") (name "Net-(VR2A-1_1)") (class "Default")
      (node (ref "R18") (pin "2") (pinfunction "2_2") (pintype "passive"))
      (node (ref "VR2") (pin "1") (pinfunction "1_1_1") (pintype "passive"))
    )
    (net (code "62") (name "Net-(VR2B-1_1)") (class "Default")
      (node (ref "R37") (pin "2") (pinfunction "2_2") (pintype "passive"))
      (node (ref "VR2") (pin "1'") (pinfunction "1_1_1'") (pintype "passive"))
    )
    (net (code "63") (name "Net-(VR3A-1_1)") (class "Default")
      (node (ref "R35") (pin "2") (pinfunction "2_2") (pintype "passive"))
      (node (ref "VR3") (pin "1") (pinfunction "1_1_1") (pintype "passive"))
    )
    (net (code "64") (name "Net-(VR3B-1_1)") (class "Default")
      (node (ref "R30") (pin "2") (pinfunction "2_2") (pintype "passive"))
      (node (ref "VR3") (pin "1'") (pinfunction "1_1_1'") (pintype "passive"))
    )
    (net (code "65") (name "Net-(VR4A-1_1)") (class "Default")
      (node (ref "R34") (pin "2") (pinfunction "2_2") (pintype "passive"))
      (node (ref "VR4") (pin "1") (pinfunction "1_1_1") (pintype "passive"))
    )
    (net (code "66") (name "Net-(VR4B-1_1)") (class "Default")
      (node (ref "R29") (pin "2") (pinfunction "2_2") (pintype "passive"))
      (node (ref "VR4") (pin "1'") (pinfunction "1_1_1'") (pintype "passive"))
    )
    (net (code "67") (name "unconnected-(R47-Pad1)") (class "Default")
      (node (ref "R47") (pin "1") (pinfunction "1_1") (pintype "passive"))
    )
  )
)
